# passthru.net
KiCad netlist of a schematic drawn in EAGLE
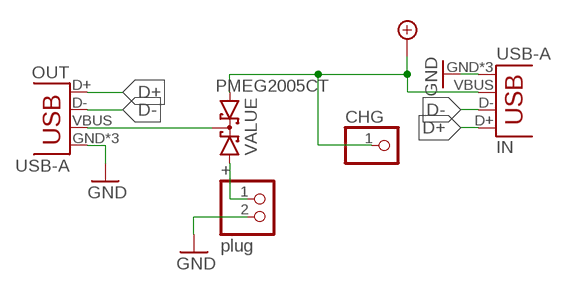
[diagram p0: schematic, sheet 1]

(export (version "E")
  (design (tool "Eeschema 10.0.6"))
  (components
    (comp (ref "+")
      (value "plug")
      (footprint "eagle-import:1X02")
      (libsource (lib "eagle-import") (part "PINHD-1X2"))
    )
    (comp (ref "CHG")
      (value "PINHD-1X1")
      (footprint "eagle-import:1X01")
      (libsource (lib "eagle-import") (part "PINHD-1X1"))
    )
    (comp (ref "IN")
      (value "USB-A")
      (footprint "eagle-import:USB-A-H")
      (libsource (lib "eagle-import") (part "USB-A"))
    )
    (comp (ref "OUT")
      (value "USB-A")
      (footprint "eagle-import:USB-A-H")
      (libsource (lib "eagle-import") (part "USB-A"))
    )
    (comp (ref "PMEG2005CT")
      (value "BAT54C")
      (footprint "eagle-import:SOT23")
      (libsource (lib "eagle-import") (part "BAT54C"))
    )
  )
  (nets
    (net (code "1") (name "+5V") (class "Default")
      (node (ref "CHG") (pin "1") (pinfunction "1_1") (pintype "passive"))
      (node (ref "IN") (pin "VBUS") (pinfunction "VBUS_VBUS") (pintype "bidirectional"))
      (node (ref "PMEG2005CT") (pin "1") (pinfunction "A1_1") (pintype "passive"))
    )
    (net (code "2") (name "D+") (class "Default")
      (node (ref "IN") (pin "D+") (pinfunction "D+_D+") (pintype "bidirectional"))
      (node (ref "OUT") (pin "D+") (pinfunction "D+_D+") (pintype "bidirectional"))
    )
    (net (code "3") (name "D-") (class "Default")
      (node (ref "IN") (pin "D-") (pinfunction "D-_D-") (pintype "bidirectional"))
      (node (ref "OUT") (pin "D-") (pinfunction "D-_D-") (pintype "bidirectional"))
    )
    (net (code "4") (name "GND") (class "Default")
      (node (ref "+") (pin "2") (pinfunction "2_2") (pintype "passive"))
      (node (ref "IN") (pin "GND") (pinfunction "GND_GND") (pintype "bidirectional"))
      (node (ref "IN") (pin "GND2") (pinfunction "GND_GND2") (pintype "bidirectional"))
      (node (ref "IN") (pin "GND3") (pinfunction "GND_GND3") (pintype "bidirectional"))
      (node (ref "OUT") (pin "GND") (pinfunction "GND_GND") (pintype "bidirectional"))
      (node (ref "OUT") (pin "GND2") (pinfunction "GND_GND2") (pintype "bidirectional"))
      (node (ref "OUT") (pin "GND3") (pinfunction "GND_GND3") (pintype "bidirectional"))
    )
    (net (code "5") (name "Net-(PMEG2005CT-A2)") (class "Default")
      (node (ref "+") (pin "1") (pinfunction "1_1") (pintype "passive"))
      (node (ref "PMEG2005CT") (pin "2") (pinfunction "A2_2") (pintype "passive"))
    )
    (net (code "6") (name "Net-(PMEG2005CT-CC)") (class "Default")
      (node (ref "OUT") (pin "VBUS") (pinfunction "VBUS_VBUS") (pintype "bidirectional"))
      (node (ref "PMEG2005CT") (pin "3") (pinfunction "CC_3") (pintype "passive"))
    )
  )
)
